# TinyFIR.net
KiCad netlist of a schematic drawn in Altium Designer
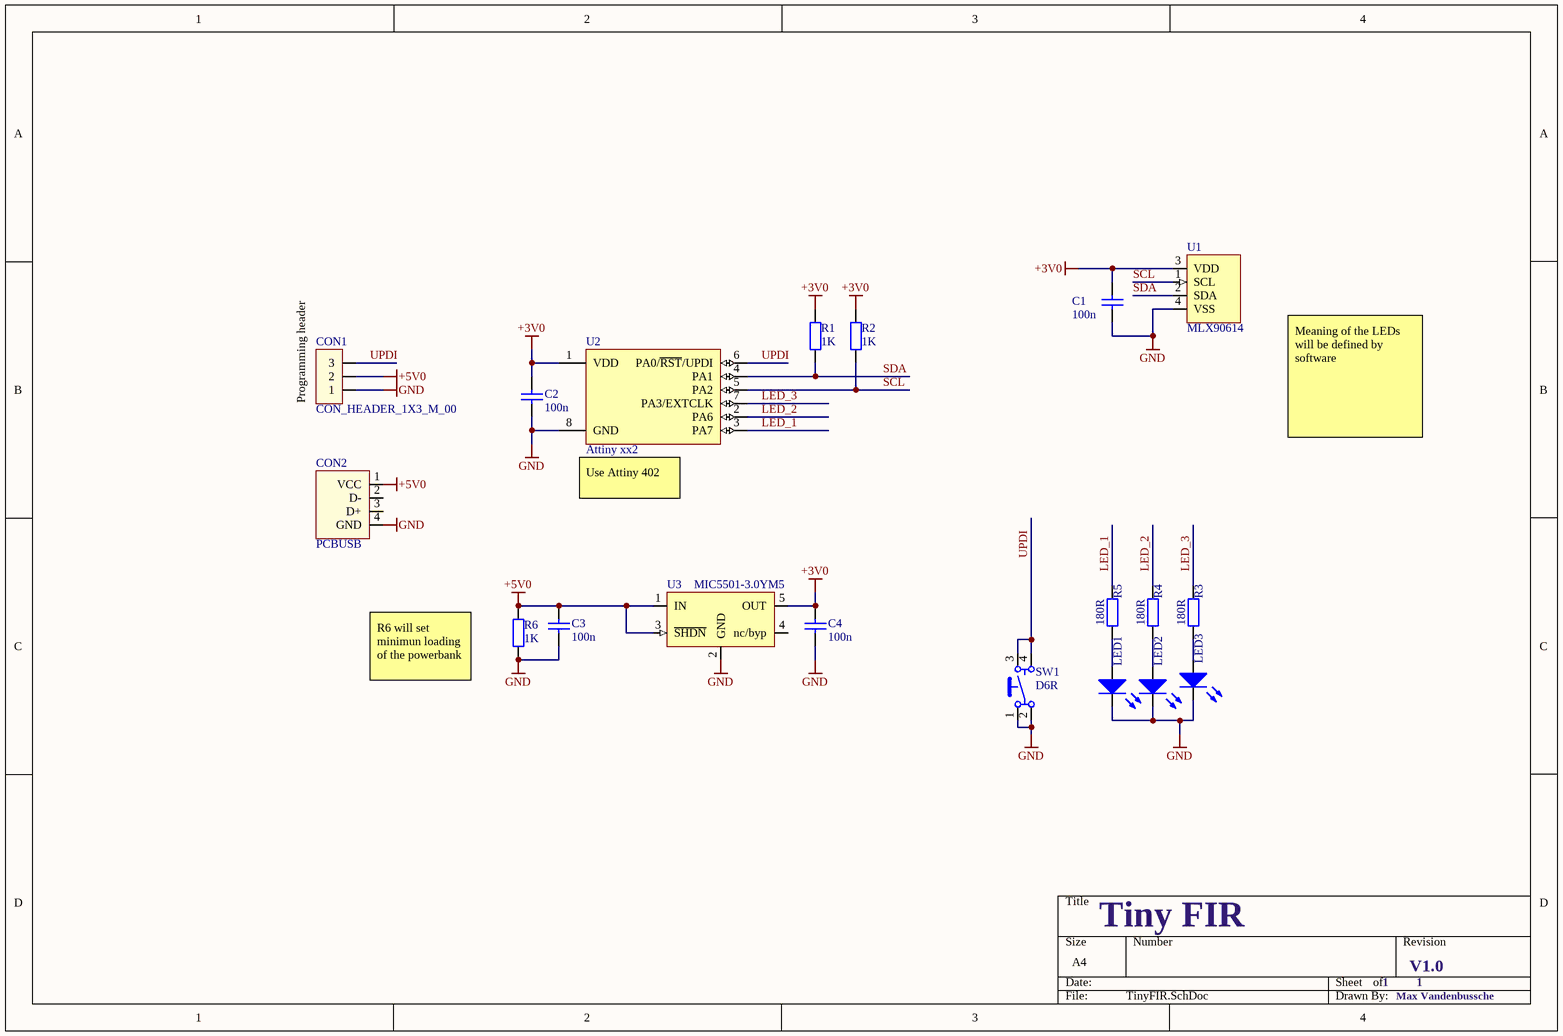
[diagram p0: TinyFIR.SchDoc]

(export (version "E")
  (design (tool "Eeschema 10.0.6"))
  (components
    (comp (ref "C1")
      (value "100n")
      (footprint "CAPC1608[0603]N")
      (description "CAPACITOR Ceramic Multi-Layer X7R; 100nF; 50V; 0603; Tolerance, +/-10%; Temp, op. -55°C to +125°C")
      (fields
        (field (name "VOLTAGE") "50V")
        (field (name "MANUFACTURER") "Samsung")
        (field (name "PUBLISHER") "PDS")
      )
      (libsource (lib "CapacitorCer0603") (part "CAPC_100n_0603"))
    )
    (comp (ref "C2")
      (value "100n")
      (footprint "CAPC1608[0603]N")
      (description "CAPACITOR Ceramic Multi-Layer X7R; 100nF; 50V; 0603; Tolerance, +/-10%; Temp, op. -55°C to +125°C")
      (fields
        (field (name "VOLTAGE") "50V")
        (field (name "MANUFACTURER") "Samsung")
        (field (name "PUBLISHER") "PDS")
      )
      (libsource (lib "CapacitorCer0603") (part "CAPC_100n_0603"))
    )
    (comp (ref "C3")
      (value "100n")
      (footprint "CAPC1608[0603]N")
      (description "CAPACITOR Ceramic Multi-Layer X7R; 100nF; 50V; 0603; Tolerance, +/-10%; Temp, op. -55°C to +125°C")
      (fields
        (field (name "VOLTAGE") "50V")
        (field (name "MANUFACTURER") "Samsung")
        (field (name "PUBLISHER") "PDS")
      )
      (libsource (lib "CapacitorCer0603") (part "CAPC_100n_0603"))
    )
    (comp (ref "C4")
      (value "100n")
      (footprint "CAPC1608[0603]N")
      (description "CAPACITOR Ceramic Multi-Layer X7R; 100nF; 50V; 0603; Tolerance, +/-10%; Temp, op. -55°C to +125°C")
      (fields
        (field (name "VOLTAGE") "50V")
        (field (name "MANUFACTURER") "Samsung")
        (field (name "PUBLISHER") "PDS")
      )
      (libsource (lib "CapacitorCer0603") (part "CAPC_100n_0603"))
    )
    (comp (ref "CON1")
      (value "CON_HEADER_1X3_M_00")
      (footprint "CON_HEADER_1X3_M_00")
      (description "Header, 1x3 pins, pitch 2.54mm, Male, Straight")
      (fields (field (name "PUBLISHER") "SLE"))
      (libsource (lib "Connectors") (part "CON_HEADER_1X3_M_00"))
    )
    (comp (ref "CON2")
      (value "PCBUSB")
      (footprint "PCB_USB")
      (description "USB A PCB connector")
      (fields (field (name "MANUFACTURER") "Amphenol") (field (name "PUBLISHER") "GDI"))
      (libsource (lib "Melexis_bot") (part "CON_USB_A_PCB"))
    )
    (comp (ref "LED1")
      (value "KP-2012SRC")
      (footprint "DIO2012[0805]")
      (description "LED SMD 0805 super bright red clear")
      (fields (field (name "PUBLISHER") "Altium/vso"))
      (libsource (lib "Semiconductor_Discrete") (part "KP-2012SRC"))
    )
    (comp (ref "LED2")
      (value "KP-2012SYC")
      (footprint "DIO2012[0805]")
      (description "LED SMD 0805 super bright yellow clear")
      (fields (field (name "PUBLISHER") "Altium/vso"))
      (libsource (lib "Semiconductor_Discrete") (part "KP-2012SYC"))
    )
    (comp (ref "LED3")
      (value "KP-2012MGC")
      (footprint "DIO2012[0805]")
      (description "LED SMD 0805 mega green clear")
      (fields (field (name "PUBLISHER") "Altium/vso"))
      (libsource (lib "Semiconductor_Discrete") (part "KP-2012MGC"))
    )
    (comp (ref "R1")
      (value "1K")
      (footprint "RESC1608[0603]N")
      (description "Resistor Thick Film; 1K; 0603; 0.1W; 1%; 50V; 100ppm/DegC")
      (fields (field (name "TOLERANCE") "1%") (field (name "PUBLISHER") "PDS"))
      (libsource (lib "Resistor0603") (part "RESC_1K_0603"))
    )
    (comp (ref "R2")
      (value "1K")
      (footprint "RESC1608[0603]N")
      (description "Resistor Thick Film; 1K; 0603; 0.1W; 1%; 50V; 100ppm/DegC")
      (fields (field (name "TOLERANCE") "1%") (field (name "PUBLISHER") "PDS"))
      (libsource (lib "Resistor0603") (part "RESC_1K_0603"))
    )
    (comp (ref "R3")
      (value "180R")
      (footprint "RESC1608[0603]N")
      (description "Resistor Thick Film; 180R; 0603; 0.1W; 1%; 50V; 100ppm/DegC")
      (fields (field (name "TOLERANCE") "1%") (field (name "PUBLISHER") "PDS"))
      (libsource (lib "Resistor0603") (part "RESC_180R_0603"))
    )
    (comp (ref "R4")
      (value "180R")
      (footprint "RESC1608[0603]N")
      (description "Resistor Thick Film; 180R; 0603; 0.1W; 1%; 50V; 100ppm/DegC")
      (fields (field (name "TOLERANCE") "1%") (field (name "PUBLISHER") "PDS"))
      (libsource (lib "Resistor0603") (part "RESC_180R_0603"))
    )
    (comp (ref "R5")
      (value "180R")
      (footprint "RESC1608[0603]N")
      (description "Resistor Thick Film; 180R; 0603; 0.1W; 1%; 50V; 100ppm/DegC")
      (fields (field (name "TOLERANCE") "1%") (field (name "PUBLISHER") "PDS"))
      (libsource (lib "Resistor0603") (part "RESC_180R_0603"))
    )
    (comp (ref "R6")
      (value "1K")
      (footprint "RESC1608[0603]N")
      (description "Resistor Thick Film; 1K; 0603; 0.1W; 1%; 50V; 100ppm/DegC")
      (fields (field (name "TOLERANCE") "1%") (field (name "PUBLISHER") "PDS"))
      (libsource (lib "Resistor0603") (part "RESC_1K_0603"))
    )
    (comp (ref "SW1")
      (value "D6R")
      (footprint "SW_SPST_PB_CK")
      (description "SPST Momentary Key Switches")
      (fields (field (name "MANUFACTURER") "TE connectivity") (field (name "PUBLISHER") "GDI"))
      (libsource (lib "Melexis_bot") (part "SW_SPST_PB_L"))
    )
    (comp (ref "U1")
      (value "MLX90614")
      (footprint "MLX90614_**C")
      (description "MLX90614 Infra Red Thermometer in TO-39")
      (fields (field (name "PUBLISHER") "GDI"))
      (libsource (lib "Melexis_bot") (part "MLX90614"))
    )
    (comp (ref "U2")
      (value "Attiny xx2")
      (footprint "SOIC127P600-8_straight")
      (description "AVR® Microcontroller with Core Independent Peripherals\r\nand picoPower® Technology")
      (libsource (lib "TinyFir_PCB") (part "Attiny_xy2"))
    )
    (comp (ref "U3")
      (value "MIC5501-3.0YM5")
      (footprint "SOT23-5")
      (description "Voltage Regulator, FIxed LDO, Vo=+3V, Io=300mA, SOT23-5")
      (fields (field (name "MANUFACTURER") "MICROCHIP") (field (name "PUBLISHER") "DTL"))
      (libsource (lib "MLX_Devices") (part "MCP1801T-1202I/OT"))
    )
  )
  (nets
    (net (code "1") (name "+3V0") (class "Default")
      (node (ref "C1") (pin "2") (pinfunction "2_2") (pintype "passive"))
      (node (ref "C2") (pin "2") (pinfunction "2_2") (pintype "passive"))
      (node (ref "C4") (pin "2") (pinfunction "2_2") (pintype "passive"))
      (node (ref "R1") (pin "2") (pinfunction "2_2") (pintype "passive"))
      (node (ref "R2") (pin "2") (pinfunction "2_2") (pintype "passive"))
      (node (ref "U1") (pin "3") (pinfunction "VDD_3") (pintype "power_in"))
      (node (ref "U2") (pin "1") (pinfunction "VDD_1") (pintype "power_in"))
      (node (ref "U3") (pin "5") (pinfunction "OUT_5") (pintype "power_in"))
    )
    (net (code "2") (name "+5V0") (class "Default")
      (node (ref "C3") (pin "2") (pinfunction "2_2") (pintype "passive"))
      (node (ref "CON1") (pin "2") (pinfunction "2_2") (pintype "passive"))
      (node (ref "CON2") (pin "1") (pinfunction "VCC_1") (pintype "passive"))
      (node (ref "R6") (pin "2") (pinfunction "2_2") (pintype "passive"))
      (node (ref "U3") (pin "1") (pinfunction "IN_1") (pintype "power_in"))
      (node (ref "U3") (pin "3") (pinfunction "~{SHDN}_3") (pintype "input"))
    )
    (net (code "3") (name "/LED_1") (class "Default")
      (node (ref "R5") (pin "2") (pinfunction "2_2") (pintype "passive"))
      (node (ref "U2") (pin "3") (pinfunction "PA7_3") (pintype "bidirectional"))
    )
    (net (code "4") (name "/LED_2") (class "Default")
      (node (ref "R4") (pin "2") (pinfunction "2_2") (pintype "passive"))
      (node (ref "U2") (pin "2") (pinfunction "PA6_2") (pintype "bidirectional"))
    )
    (net (code "5") (name "/LED_3") (class "Default")
      (node (ref "R3") (pin "2") (pinfunction "2_2") (pintype "passive"))
      (node (ref "U2") (pin "7") (pinfunction "PA3/EXTCLK_7") (pintype "bidirectional"))
    )
    (net (code "6") (name "/SCL") (class "Default")
      (node (ref "R2") (pin "1") (pinfunction "1_1") (pintype "passive"))
      (node (ref "U1") (pin "1") (pinfunction "SCL_1") (pintype "input"))
      (node (ref "U2") (pin "5") (pinfunction "PA2_5") (pintype "bidirectional"))
    )
    (net (code "7") (name "/SDA") (class "Default")
      (node (ref "R1") (pin "1") (pinfunction "1_1") (pintype "passive"))
      (node (ref "U1") (pin "2") (pinfunction "SDA_2") (pintype "bidirectional"))
      (node (ref "U2") (pin "4") (pinfunction "PA1_4") (pintype "bidirectional"))
    )
    (net (code "8") (name "/UPDI") (class "Default")
      (node (ref "CON1") (pin "3") (pinfunction "3_3") (pintype "passive"))
      (node (ref "SW1") (pin "3") (pinfunction "C_3") (pintype "passive"))
      (node (ref "SW1") (pin "4") (pinfunction "D_4") (pintype "passive"))
      (node (ref "U2") (pin "6") (pinfunction "PA0/~{RST}/UPDI_6") (pintype "bidirectional"))
    )
    (net (code "9") (name "GND") (class "Default")
      (node (ref "C1") (pin "1") (pinfunction "1_1") (pintype "passive"))
      (node (ref "C2") (pin "1") (pinfunction "1_1") (pintype "passive"))
      (node (ref "C3") (pin "1") (pinfunction "1_1") (pintype "passive"))
      (node (ref "C4") (pin "1") (pinfunction "1_1") (pintype "passive"))
      (node (ref "CON1") (pin "1") (pinfunction "1_1") (pintype "passive"))
      (node (ref "CON2") (pin "4") (pinfunction "GND_4") (pintype "passive"))
      (node (ref "LED1") (pin "1") (pinfunction "K_1") (pintype "passive"))
      (node (ref "LED2") (pin "1") (pinfunction "K_1") (pintype "passive"))
      (node (ref "LED3") (pin "1") (pinfunction "K_1") (pintype "passive"))
      (node (ref "R6") (pin "1") (pinfunction "1_1") (pintype "passive"))
      (node (ref "SW1") (pin "1") (pinfunction "A_1") (pintype "passive"))
      (node (ref "SW1") (pin "2") (pinfunction "B_2") (pintype "passive"))
      (node (ref "U1") (pin "4") (pinfunction "VSS_4") (pintype "power_in"))
      (node (ref "U2") (pin "8") (pinfunction "GND_8") (pintype "power_in"))
      (node (ref "U3") (pin "2") (pinfunction "GND_2") (pintype "power_in"))
    )
    (net (code "10") (name "Net-(LED1-A)") (class "Default")
      (node (ref "LED1") (pin "2") (pinfunction "A_2") (pintype "passive"))
      (node (ref "R5") (pin "1") (pinfunction "1_1") (pintype "passive"))
    )
    (net (code "11") (name "Net-(LED2-A)") (class "Default")
      (node (ref "LED2") (pin "2") (pinfunction "A_2") (pintype "passive"))
      (node (ref "R4") (pin "1") (pinfunction "1_1") (pintype "passive"))
    )
    (net (code "12") (name "Net-(LED3-A)") (class "Default")
      (node (ref "LED3") (pin "2") (pinfunction "A_2") (pintype "passive"))
      (node (ref "R3") (pin "1") (pinfunction "1_1") (pintype "passive"))
    )
    (net (code "13") (name "unconnected-(CON2-D+-Pad3)") (class "Default")
      (node (ref "CON2") (pin "3") (pinfunction "D+_3") (pintype "passive"))
    )
    (net (code "14") (name "unconnected-(CON2-D--Pad2)") (class "Default")
      (node (ref "CON2") (pin "2") (pinfunction "D-_2") (pintype "passive"))
    )
    (net (code "15") (name "unconnected-(U3-nc{slash}byp-Pad4)") (class "Default")
      (node (ref "U3") (pin "4") (pinfunction "nc/byp_4") (pintype "passive"))
    )
  )
)
